# 4_-_Ethernet_phy.net
KiCad netlist of a schematic drawn in Altium Designer
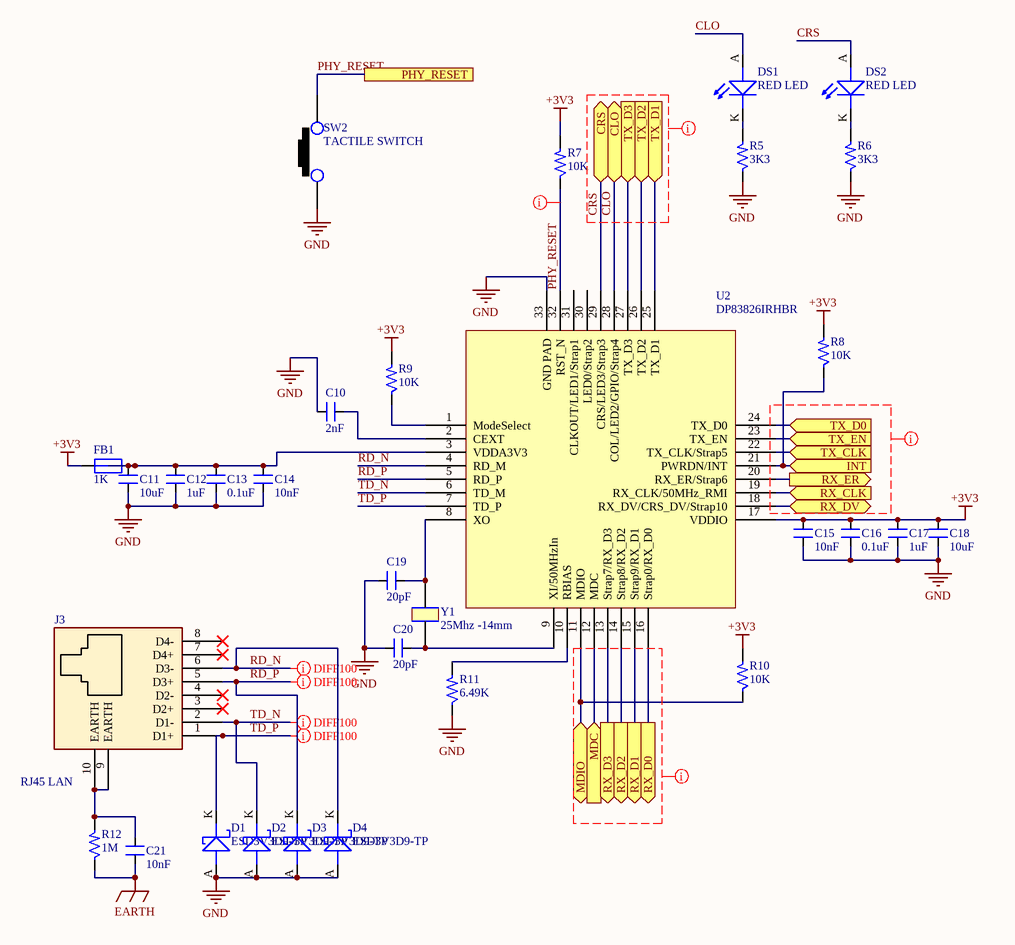
[diagram p0: [4] - Ethernet phy.SchDoc]

(export (version "E")
  (design (tool "Eeschema 10.0.6"))
  (components
    (comp (ref "C10")
      (value "2nF")
      (footprint "CAP_0805")
      (description "2000pF ±10% 50V Ceramic Capacitor X7R 0805 (2012 Metric)")
      (fields
        (field (name "MANUFACTURER") "Samsung Electro-Mechanics")
        (field (name "MANUFACTURER PART NUMBER") "CL21B202KBANNNC")
      )
      (libsource (lib "ESTEEMPCBLIB") (part "CAP_2nF-50V-10%-0805"))
    )
    (comp (ref "C11")
      (value "10uF")
      (footprint "CAP_1206")
      (description "10µF ±10% 50V Ceramic Capacitor X7R 1206 (3216 Metric)")
      (fields
        (field (name "MANUFACTURER") "KEMET")
        (field (name "MANUFACTURER PART NUMBER") "CL31B106KBHNNNE")
      )
      (libsource (lib "ESTEEMPCBLIB") (part "CAP_10uF-50V-10%-1206"))
    )
    (comp (ref "C12")
      (value "1uF")
      (footprint "CAP_0805")
      (description "1µF ±5% 50V Ceramic Capacitor X7R 0805 (2012 Metric)")
      (fields
        (field (name "MANUFACTURER") "Samsung")
        (field (name "MANUFACTURER PART NUMBER") "CC0805JKX7R9BB105")
      )
      (libsource (lib "ESTEEMPCBLIB") (part "CAP_1uF-50V-5%-0805"))
    )
    (comp (ref "C13")
      (value "0.1uF")
      (footprint "CAP_0805")
      (description "0.1µF ±5% 50V Ceramic Capacitor X7R 0805 (2012 Metric)")
      (fields
        (field (name "MANUFACTURER") "AVX Corporation")
        (field (name "MANUFACTURER PART NUMBER") "08055C104JAT4A")
      )
      (libsource (lib "ESTEEMPCBLIB") (part "CAP_0.1uF-50V-5%-0805"))
    )
    (comp (ref "C14")
      (value "10nF")
      (footprint "CAP_0805")
      (description "10000pF ±10% 50V Ceramic Capacitor X7R 0805 (2012 Metric)")
      (fields
        (field (name "MANUFACTURER") "Samsung")
        (field (name "MANUFACTURER PART NUMBER") "C0805C103K5RECAUTO")
      )
      (libsource (lib "ESTEEMPCBLIB") (part "CAP_10nF-50V-10%-0805"))
    )
    (comp (ref "C15")
      (value "10nF")
      (footprint "CAP_0805")
      (description "10000pF ±10% 50V Ceramic Capacitor X7R 0805 (2012 Metric)")
      (fields
        (field (name "MANUFACTURER") "Samsung")
        (field (name "MANUFACTURER PART NUMBER") "C0805C103K5RECAUTO")
      )
      (libsource (lib "ESTEEMPCBLIB") (part "CAP_10nF-50V-10%-0805"))
    )
    (comp (ref "C16")
      (value "0.1uF")
      (footprint "CAP_0805")
      (description "0.1µF ±5% 50V Ceramic Capacitor X7R 0805 (2012 Metric)")
      (fields
        (field (name "MANUFACTURER") "AVX Corporation")
        (field (name "MANUFACTURER PART NUMBER") "08055C104JAT4A")
      )
      (libsource (lib "ESTEEMPCBLIB") (part "CAP_0.1uF-50V-5%-0805"))
    )
    (comp (ref "C17")
      (value "1uF")
      (footprint "CAP_0805")
      (description "1µF ±5% 50V Ceramic Capacitor X7R 0805 (2012 Metric)")
      (fields
        (field (name "MANUFACTURER") "Samsung")
        (field (name "MANUFACTURER PART NUMBER") "CC0805JKX7R9BB105")
      )
      (libsource (lib "ESTEEMPCBLIB") (part "CAP_1uF-50V-5%-0805"))
    )
    (comp (ref "C18")
      (value "10uF")
      (footprint "CAP_1206")
      (description "10µF ±10% 50V Ceramic Capacitor X7R 1206 (3216 Metric)")
      (fields
        (field (name "MANUFACTURER") "KEMET")
        (field (name "MANUFACTURER PART NUMBER") "CL31B106KBHNNNE")
      )
      (libsource (lib "ESTEEMPCBLIB") (part "CAP_10uF-50V-10%-1206"))
    )
    (comp (ref "C19")
      (value "20pF")
      (footprint "CAP_0805")
      (description "±10% 50V Ceramic Capacitor C0G, NP0 0805 (2012 Metric)")
      (fields
        (field (name "MANUFACTURER") "AVX Corporation")
        (field (name "MANUFACTURER PART NUMBER") "08055A200KAT2A")
      )
      (libsource (lib "ESTEEMPCBLIB") (part "CAP_20pF-50V-10%-0805"))
    )
    (comp (ref "C20")
      (value "20pF")
      (footprint "CAP_0805")
      (description "±10% 50V Ceramic Capacitor C0G, NP0 0805 (2012 Metric)")
      (fields
        (field (name "MANUFACTURER") "AVX Corporation")
        (field (name "MANUFACTURER PART NUMBER") "08055A200KAT2A")
      )
      (libsource (lib "ESTEEMPCBLIB") (part "CAP_20pF-50V-10%-0805"))
    )
    (comp (ref "C21")
      (value "10nF")
      (footprint "CAP_P196_102X287_H332_RAD_TH")
      (description "10000pF ±10% 1000V (1kV) Ceramic Capacitor X7R Radial")
      (fields
        (field (name "MANUFACTURER") "Yageo")
        (field (name "MANUFACTURER PART NUMBER") "RDER73A103K2K1H03B")
      )
      (libsource (lib "ESTEEMPCBLIB") (part "CAP_10nF-1KV-10%-RAD-TH"))
    )
    (comp (ref "D1")
      (value "ESD3V3D9-TP")
      (footprint "DIO_SOD-923")
      (description "8.8V Clamp 5A (8/20µs) Ipp Tvs Diode Surface Mount SOD-923")
      (fields (field (name "MANUFACTURER") "Micro Commercial Co"))
      (libsource (lib "ESTEEMPCBLIB") (part "DIO-T_3.3V-8.8V-SOD923"))
    )
    (comp (ref "D2")
      (value "ESD3V3D9-TP")
      (footprint "DIO_SOD-923")
      (description "8.8V Clamp 5A (8/20µs) Ipp Tvs Diode Surface Mount SOD-923")
      (fields (field (name "MANUFACTURER") "Micro Commercial Co"))
      (libsource (lib "ESTEEMPCBLIB") (part "DIO-T_3.3V-8.8V-SOD923"))
    )
    (comp (ref "D3")
      (value "ESD3V3D9-TP")
      (footprint "DIO_SOD-923")
      (description "8.8V Clamp 5A (8/20µs) Ipp Tvs Diode Surface Mount SOD-923")
      (fields (field (name "MANUFACTURER") "Micro Commercial Co"))
      (libsource (lib "ESTEEMPCBLIB") (part "DIO-T_3.3V-8.8V-SOD923"))
    )
    (comp (ref "D4")
      (value "ESD3V3D9-TP")
      (footprint "DIO_SOD-923")
      (description "8.8V Clamp 5A (8/20µs) Ipp Tvs Diode Surface Mount SOD-923")
      (fields (field (name "MANUFACTURER") "Micro Commercial Co"))
      (libsource (lib "ESTEEMPCBLIB") (part "DIO-T_3.3V-8.8V-SOD923"))
    )
    (comp (ref "DS1")
      (value "RED LED")
      (footprint "LED_0805")
      (description "Red 631nm LED Indication - Discrete 2V 0805 (2012 Metric)")
      (fields
        (field (name "MANUFACTURER") "Vishay Lite-On")
        (field (name "MANUFACTURER PART NUMBER") "LTST-C171KRKT")
      )
      (libsource (lib "ESTEEMPCBLIB") (part "LED_RED-2V-20mA-0805"))
    )
    (comp (ref "DS2")
      (value "RED LED")
      (footprint "LED_0805")
      (description "Red 631nm LED Indication - Discrete 2V 0805 (2012 Metric)")
      (fields
        (field (name "MANUFACTURER") "Vishay Lite-On")
        (field (name "MANUFACTURER PART NUMBER") "LTST-C171KRKT")
      )
      (libsource (lib "ESTEEMPCBLIB") (part "LED_RED-2V-20mA-0805"))
    )
    (comp (ref "FB1")
      (value "1K")
      (footprint "IND_0805")
      (description "1 kOhms @ 100MHz 1 Power Line Ferrite Bead 0805 (2012 Metric) 1.6A")
      (fields
        (field (name "MANUFACTURER") "Laird")
        (field (name "MANUFACTURER PART NUMBER") "BLM21SP102SH1D")
      )
      (libsource (lib "ESTEEMPCBLIB") (part "FB_1K-100MHZ-1.6A-0805"))
    )
    (comp (ref "J3")
      (value "RJ45 LAN")
      (footprint "CON10_P106_RJ45_TH_ST")
      (description "8 Pins, 2 Row 2.54mm Pitch, right angle Connector, male")
      (fields
        (field (name "MANUFACTURER") "Assmann")
        (field (name "MANUFACTURER PART NUMBER") "A-2004-2-4-LPS-N-R")
      )
      (libsource (lib "ESTEEMPCBLIB") (part "CON-SKT-RJ_8C8P-RA-TH"))
    )
    (comp (ref "R5")
      (value "3K3")
      (footprint "RES_0603")
      (description "3.3 kOhms ±1% 0.1W, 1/10W Chip Resistor 0603 (1608 Metric) Automotive AEC-Q200 Thick Film")
      (fields (field (name "MANUFACTURER") "Wilson") (field (name "MANUFACTURER PART NUMBER") "WR06X3301FTL"))
      (libsource (lib "ESTEEMPCBLIB") (part "RES_3.3K-0.1W-1%-0603"))
    )
    (comp (ref "R6")
      (value "3K3")
      (footprint "RES_0603")
      (description "3.3 kOhms ±1% 0.1W, 1/10W Chip Resistor 0603 (1608 Metric) Automotive AEC-Q200 Thick Film")
      (fields (field (name "MANUFACTURER") "Wilson") (field (name "MANUFACTURER PART NUMBER") "WR06X3301FTL"))
      (libsource (lib "ESTEEMPCBLIB") (part "RES_3.3K-0.1W-1%-0603"))
    )
    (comp (ref "R7")
      (value "10K")
      (footprint "RES_0603")
      (description "10 kOhms ±1% 0.1W, 1/10W Chip Resistor 0603 (1608 Metric) Automotive AEC-Q200 Thick Film")
      (fields (field (name "MANUFACTURER") "Walsin") (field (name "MANUFACTURER PART NUMBER") "WR06X1002FTL"))
      (libsource (lib "ESTEEMPCBLIB") (part "RES_10K-0.1W-1%-0603"))
    )
    (comp (ref "R8")
      (value "10K")
      (footprint "RES_0603")
      (description "10 kOhms ±1% 0.1W, 1/10W Chip Resistor 0603 (1608 Metric) Automotive AEC-Q200 Thick Film")
      (fields (field (name "MANUFACTURER") "Walsin") (field (name "MANUFACTURER PART NUMBER") "WR06X1002FTL"))
      (libsource (lib "ESTEEMPCBLIB") (part "RES_10K-0.1W-1%-0603"))
    )
    (comp (ref "R9")
      (value "10K")
      (footprint "RES_0603")
      (description "10 kOhms ±1% 0.1W, 1/10W Chip Resistor 0603 (1608 Metric) Automotive AEC-Q200 Thick Film")
      (fields (field (name "MANUFACTURER") "Walsin") (field (name "MANUFACTURER PART NUMBER") "WR06X1002FTL"))
      (libsource (lib "ESTEEMPCBLIB") (part "RES_10K-0.1W-1%-0603"))
    )
    (comp (ref "R10")
      (value "10K")
      (footprint "RES_0603")
      (description "10 kOhms ±1% 0.1W, 1/10W Chip Resistor 0603 (1608 Metric) Automotive AEC-Q200 Thick Film")
      (fields (field (name "MANUFACTURER") "Walsin") (field (name "MANUFACTURER PART NUMBER") "WR06X1002FTL"))
      (libsource (lib "ESTEEMPCBLIB") (part "RES_10K-0.1W-1%-0603"))
    )
    (comp (ref "R11")
      (value "6.49K")
      (footprint "RES_0805")
      (description "6.49 kOhms ±1% 0.125W, 1/8W Chip Resistor 0805 (2012 Metric) Moisture Resistant Thick Film")
      (fields
        (field (name "MANUFACTURER") "Stackpole Electronics")
        (field (name "MANUFACTURER PART NUMBER") "RC0805FR-076K49L")
      )
      (libsource (lib "ESTEEMPCBLIB") (part "RES_6.49K-0.125W-1%-0805"))
    )
    (comp (ref "R12")
      (value "1M")
      (footprint "RES_1206")
      (fields (field (name "MANUFACTURER") "Walsin") (field (name "MANUFACTURER PART NUMBER") "WR12X1004FTL"))
      (libsource (lib "ESTEEMPCBLIB") (part "RES_1M-0.25W-1%-1206"))
    )
    (comp (ref "SW2")
      (value "TACTILE SWITCH")
      (footprint "SW_342_SMD")
      (description "Tactile Switch SPST-NO Top Actuated Surface Mount")
      (fields
        (field (name "MANUFACTURER") "ITT C&K")
        (field (name "MANUFACTURER PART NUMBER") "RS-282G05A3-SMRT")
      )
      (libsource (lib "ESTEEMPCBLIB") (part "SW1_RS-282G05A3-SMRT-SMD"))
    )
    (comp (ref "U2")
      (value "DP83826IRHBR")
      (footprint "VQFN32_19_218_23X9_SMD")
      (fields (field (name "MANUFACTURER") "Texas Instruments"))
      (libsource (lib "ESTEEMPCBLIB") (part "IC_DP83826IRHBR"))
    )
    (comp (ref "Y1")
      (value "25Mhz -14mm")
      (footprint "XTAL_314_240X47_SMD")
      (description "25MHz ±30ppm Crystal 20pF 30 Ohms HC-49/US")
      (fields
        (field (name "MANUFACTURER") "Abracon")
        (field (name "MANUFACTURER PART NUMBER") "FOXSDLF/250F-20")
      )
      (libsource (lib "ESTEEMPCBLIB") (part "XTAL_25Mhz-FOXSDLF/250F-20"))
    )
  )
  (nets
    (net (code "1") (name "+3V3") (class "Default")
      (node (ref "C15") (pin "2") (pinfunction "2_2") (pintype "passive"))
      (node (ref "C16") (pin "2") (pinfunction "2_2") (pintype "passive"))
      (node (ref "C17") (pin "2") (pinfunction "2_2") (pintype "passive"))
      (node (ref "C18") (pin "1") (pinfunction "1_1") (pintype "passive"))
      (node (ref "FB1") (pin "1") (pinfunction "1_1") (pintype "passive"))
      (node (ref "R10") (pin "2") (pinfunction "2_2") (pintype "passive"))
      (node (ref "R7") (pin "2") (pinfunction "2_2") (pintype "passive"))
      (node (ref "R8") (pin "2") (pinfunction "2_2") (pintype "passive"))
      (node (ref "R9") (pin "2") (pinfunction "2_2") (pintype "passive"))
      (node (ref "U2") (pin "17") (pinfunction "VDDIO_17") (pintype "passive"))
    )
    (net (code "2") (name "/CLO") (class "Default")
      (node (ref "DS1") (pin "A") (pinfunction "ANODE_A") (pintype "passive"))
      (node (ref "U2") (pin "28") (pinfunction "COL/LED2/GPIO/Strap4_28") (pintype "passive"))
    )
    (net (code "3") (name "/CRS") (class "Default")
      (node (ref "DS2") (pin "A") (pinfunction "ANODE_A") (pintype "passive"))
      (node (ref "U2") (pin "29") (pinfunction "CRS/LED3/Strap3_29") (pintype "passive"))
    )
    (net (code "4") (name "/INT") (class "Default")
      (node (ref "R8") (pin "1") (pinfunction "1_1") (pintype "passive"))
      (node (ref "U2") (pin "21") (pinfunction "PWRDN/INT_21") (pintype "passive"))
    )
    (net (code "5") (name "/MDC") (class "Default")
      (node (ref "U2") (pin "12") (pinfunction "MDC_12") (pintype "passive"))
    )
    (net (code "6") (name "/MDIO") (class "Default")
      (node (ref "R10") (pin "1") (pinfunction "1_1") (pintype "passive"))
      (node (ref "U2") (pin "11") (pinfunction "MDIO_11") (pintype "passive"))
    )
    (net (code "7") (name "/PHY_RESET") (class "Default")
      (node (ref "R7") (pin "1") (pinfunction "1_1") (pintype "passive"))
      (node (ref "SW2") (pin "2") (pinfunction "2_2") (pintype "passive"))
      (node (ref "U2") (pin "32") (pinfunction "RST_N_32") (pintype "passive"))
    )
    (net (code "8") (name "/RD_N") (class "Default")
      (node (ref "D4") (pin "K") (pinfunction "K_K") (pintype "passive"))
      (node (ref "J3") (pin "6") (pinfunction "D3-_6") (pintype "passive"))
      (node (ref "U2") (pin "4") (pinfunction "RD_M_4") (pintype "passive"))
    )
    (net (code "9") (name "/RD_P") (class "Default")
      (node (ref "D3") (pin "K") (pinfunction "K_K") (pintype "passive"))
      (node (ref "J3") (pin "5") (pinfunction "D3+_5") (pintype "passive"))
      (node (ref "U2") (pin "5") (pinfunction "RD_P_5") (pintype "passive"))
    )
    (net (code "10") (name "/RX_CLK") (class "Default")
      (node (ref "U2") (pin "19") (pinfunction "RX_CLK/50MHz_RMI_19") (pintype "passive"))
    )
    (net (code "11") (name "/RX_D0") (class "Default")
      (node (ref "U2") (pin "16") (pinfunction "Strap0/RX_D0_16") (pintype "passive"))
    )
    (net (code "12") (name "/RX_D1") (class "Default")
      (node (ref "U2") (pin "15") (pinfunction "Strap9/RX_D1_15") (pintype "passive"))
    )
    (net (code "13") (name "/RX_D2") (class "Default")
      (node (ref "U2") (pin "14") (pinfunction "Strap8/RX_D2_14") (pintype "passive"))
    )
    (net (code "14") (name "/RX_D3") (class "Default")
      (node (ref "U2") (pin "13") (pinfunction "Strap7/RX_D3_13") (pintype "passive"))
    )
    (net (code "15") (name "/RX_DV") (class "Default")
      (node (ref "U2") (pin "18") (pinfunction "RX_DV/CRS_DV/Strap10_18") (pintype "passive"))
    )
    (net (code "16") (name "/RX_ER") (class "Default")
      (node (ref "U2") (pin "20") (pinfunction "RX_ER/Strap6_20") (pintype "passive"))
    )
    (net (code "17") (name "/TD_N") (class "Default")
      (node (ref "D2") (pin "K") (pinfunction "K_K") (pintype "passive"))
      (node (ref "J3") (pin "2") (pinfunction "D1-_2") (pintype "passive"))
      (node (ref "U2") (pin "6") (pinfunction "TD_M_6") (pintype "passive"))
    )
    (net (code "18") (name "/TD_P") (class "Default")
      (node (ref "D1") (pin "K") (pinfunction "K_K") (pintype "passive"))
      (node (ref "J3") (pin "1") (pinfunction "D1+_1") (pintype "passive"))
      (node (ref "U2") (pin "7") (pinfunction "TD_P_7") (pintype "passive"))
    )
    (net (code "19") (name "/TX_CLK") (class "Default")
      (node (ref "U2") (pin "22") (pinfunction "TX_CLK/Strap5_22") (pintype "passive"))
    )
    (net (code "20") (name "/TX_D0") (class "Default")
      (node (ref "U2") (pin "24") (pinfunction "TX_D0_24") (pintype "passive"))
    )
    (net (code "21") (name "/TX_D1") (class "Default")
      (node (ref "U2") (pin "25") (pinfunction "TX_D1_25") (pintype "passive"))
    )
    (net (code "22") (name "/TX_D2") (class "Default")
      (node (ref "U2") (pin "26") (pinfunction "TX_D2_26") (pintype "passive"))
    )
    (net (code "23") (name "/TX_D3") (class "Default")
      (node (ref "U2") (pin "27") (pinfunction "TX_D3_27") (pintype "passive"))
    )
    (net (code "24") (name "/TX_EN") (class "Default")
      (node (ref "U2") (pin "23") (pinfunction "TX_EN_23") (pintype "passive"))
    )
    (net (code "25") (name "EARTH") (class "Default")
      (node (ref "C21") (pin "1") (pinfunction "1_1") (pintype "passive"))
      (node (ref "R12") (pin "1") (pinfunction "1_1") (pintype "passive"))
    )
    (net (code "26") (name "GND") (class "Default")
      (node (ref "C10") (pin "1") (pinfunction "1_1") (pintype "passive"))
      (node (ref "C11") (pin "2") (pinfunction "2_2") (pintype "passive"))
      (node (ref "C12") (pin "1") (pinfunction "1_1") (pintype "passive"))
      (node (ref "C13") (pin "1") (pinfunction "1_1") (pintype "passive"))
      (node (ref "C14") (pin "1") (pinfunction "1_1") (pintype "passive"))
      (node (ref "C15") (pin "1") (pinfunction "1_1") (pintype "passive"))
      (node (ref "C16") (pin "1") (pinfunction "1_1") (pintype "passive"))
      (node (ref "C17") (pin "1") (pinfunction "1_1") (pintype "passive"))
      (node (ref "C18") (pin "2") (pinfunction "2_2") (pintype "passive"))
      (node (ref "C19") (pin "1") (pinfunction "1_1") (pintype "passive"))
      (node (ref "C20") (pin "1") (pinfunction "1_1") (pintype "passive"))
      (node (ref "D1") (pin "A") (pinfunction "A_A") (pintype "passive"))
      (node (ref "D2") (pin "A") (pinfunction "A_A") (pintype "passive"))
      (node (ref "D3") (pin "A") (pinfunction "A_A") (pintype "passive"))
      (node (ref "D4") (pin "A") (pinfunction "A_A") (pintype "passive"))
      (node (ref "R11") (pin "1") (pinfunction "1_1") (pintype "passive"))
      (node (ref "R5") (pin "1") (pinfunction "1_1") (pintype "passive"))
      (node (ref "R6") (pin "1") (pinfunction "1_1") (pintype "passive"))
      (node (ref "SW2") (pin "1") (pinfunction "1_1") (pintype "passive"))
      (node (ref "U2") (pin "33") (pinfunction "GND_PAD_33") (pintype "passive"))
    )
    (net (code "27") (name "Net-(C21-Pad2)") (class "Default")
      (node (ref "C21") (pin "2") (pinfunction "2_2") (pintype "passive"))
      (node (ref "J3") (pin "10") (pinfunction "EARTH_10") (pintype "passive"))
      (node (ref "J3") (pin "9") (pinfunction "EARTH_9") (pintype "passive"))
      (node (ref "R12") (pin "2") (pinfunction "2_2") (pintype "passive"))
    )
    (net (code "28") (name "Net-(DS1-CATHODE)") (class "Default")
      (node (ref "DS1") (pin "K") (pinfunction "CATHODE_K") (pintype "passive"))
      (node (ref "R5") (pin "2") (pinfunction "2_2") (pintype "passive"))
    )
    (net (code "29") (name "Net-(DS2-CATHODE)") (class "Default")
      (node (ref "DS2") (pin "K") (pinfunction "CATHODE_K") (pintype "passive"))
      (node (ref "R6") (pin "2") (pinfunction "2_2") (pintype "passive"))
    )
    (net (code "30") (name "Net-(U2-CEXT)") (class "Default")
      (node (ref "C10") (pin "2") (pinfunction "2_2") (pintype "passive"))
      (node (ref "U2") (pin "2") (pinfunction "CEXT_2") (pintype "passive"))
    )
    (net (code "31") (name "Net-(U2-ModeSelect)") (class "Default")
      (node (ref "R9") (pin "1") (pinfunction "1_1") (pintype "passive"))
      (node (ref "U2") (pin "1") (pinfunction "ModeSelect_1") (pintype "passive"))
    )
    (net (code "32") (name "Net-(U2-RBIAS)") (class "Default")
      (node (ref "R11") (pin "2") (pinfunction "2_2") (pintype "passive"))
      (node (ref "U2") (pin "10") (pinfunction "RBIAS_10") (pintype "passive"))
    )
    (net (code "33") (name "Net-(U2-VDDA3V3)") (class "Default")
      (node (ref "C11") (pin "1") (pinfunction "1_1") (pintype "passive"))
      (node (ref "C12") (pin "2") (pinfunction "2_2") (pintype "passive"))
      (node (ref "C13") (pin "2") (pinfunction "2_2") (pintype "passive"))
      (node (ref "C14") (pin "2") (pinfunction "2_2") (pintype "passive"))
      (node (ref "FB1") (pin "2") (pinfunction "2_2") (pintype "passive"))
      (node (ref "U2") (pin "3") (pinfunction "VDDA3V3_3") (pintype "passive"))
    )
    (net (code "34") (name "Net-(U2-XI{slash}50MHzIn)") (class "Default")
      (node (ref "C20") (pin "2") (pinfunction "2_2") (pintype "passive"))
      (node (ref "U2") (pin "9") (pinfunction "XI/50MHzIn_9") (pintype "passive"))
      (node (ref "Y1") (pin "1") (pinfunction "1_1") (pintype "passive"))
    )
    (net (code "35") (name "Net-(U2-XO)") (class "Default")
      (node (ref "C19") (pin "2") (pinfunction "2_2") (pintype "passive"))
      (node (ref "U2") (pin "8") (pinfunction "XO_8") (pintype "passive"))
      (node (ref "Y1") (pin "2") (pinfunction "2_2") (pintype "passive"))
    )
    (net (code "36") (name "unconnected-(J3-D2+-Pad3)") (class "Default")
      (node (ref "J3") (pin "3") (pinfunction "D2+_3") (pintype "passive+no_connect"))
    )
    (net (code "37") (name "unconnected-(J3-D2--Pad4)") (class "Default")
      (node (ref "J3") (pin "4") (pinfunction "D2-_4") (pintype "passive+no_connect"))
    )
    (net (code "38") (name "unconnected-(J3-D4+-Pad7)") (class "Default")
      (node (ref "J3") (pin "7") (pinfunction "D4+_7") (pintype "passive+no_connect"))
    )
    (net (code "39") (name "unconnected-(J3-D4--Pad8)") (class "Default")
      (node (ref "J3") (pin "8") (pinfunction "D4-_8") (pintype "passive+no_connect"))
    )
    (net (code "40") (name "unconnected-(U2-CLKOUT{slash}LED1{slash}Strap1-Pad31)") (class "Default")
      (node (ref "U2") (pin "31") (pinfunction "CLKOUT/LED1/Strap1_31") (pintype "passive"))
    )
    (net (code "41") (name "unconnected-(U2-LED0{slash}Strap2-Pad30)") (class "Default")
      (node (ref "U2") (pin "30") (pinfunction "LED0/Strap2_30") (pintype "passive"))
    )
  )
)
